# MotorConnector.net
KiCad netlist of a schematic drawn in EAGLE
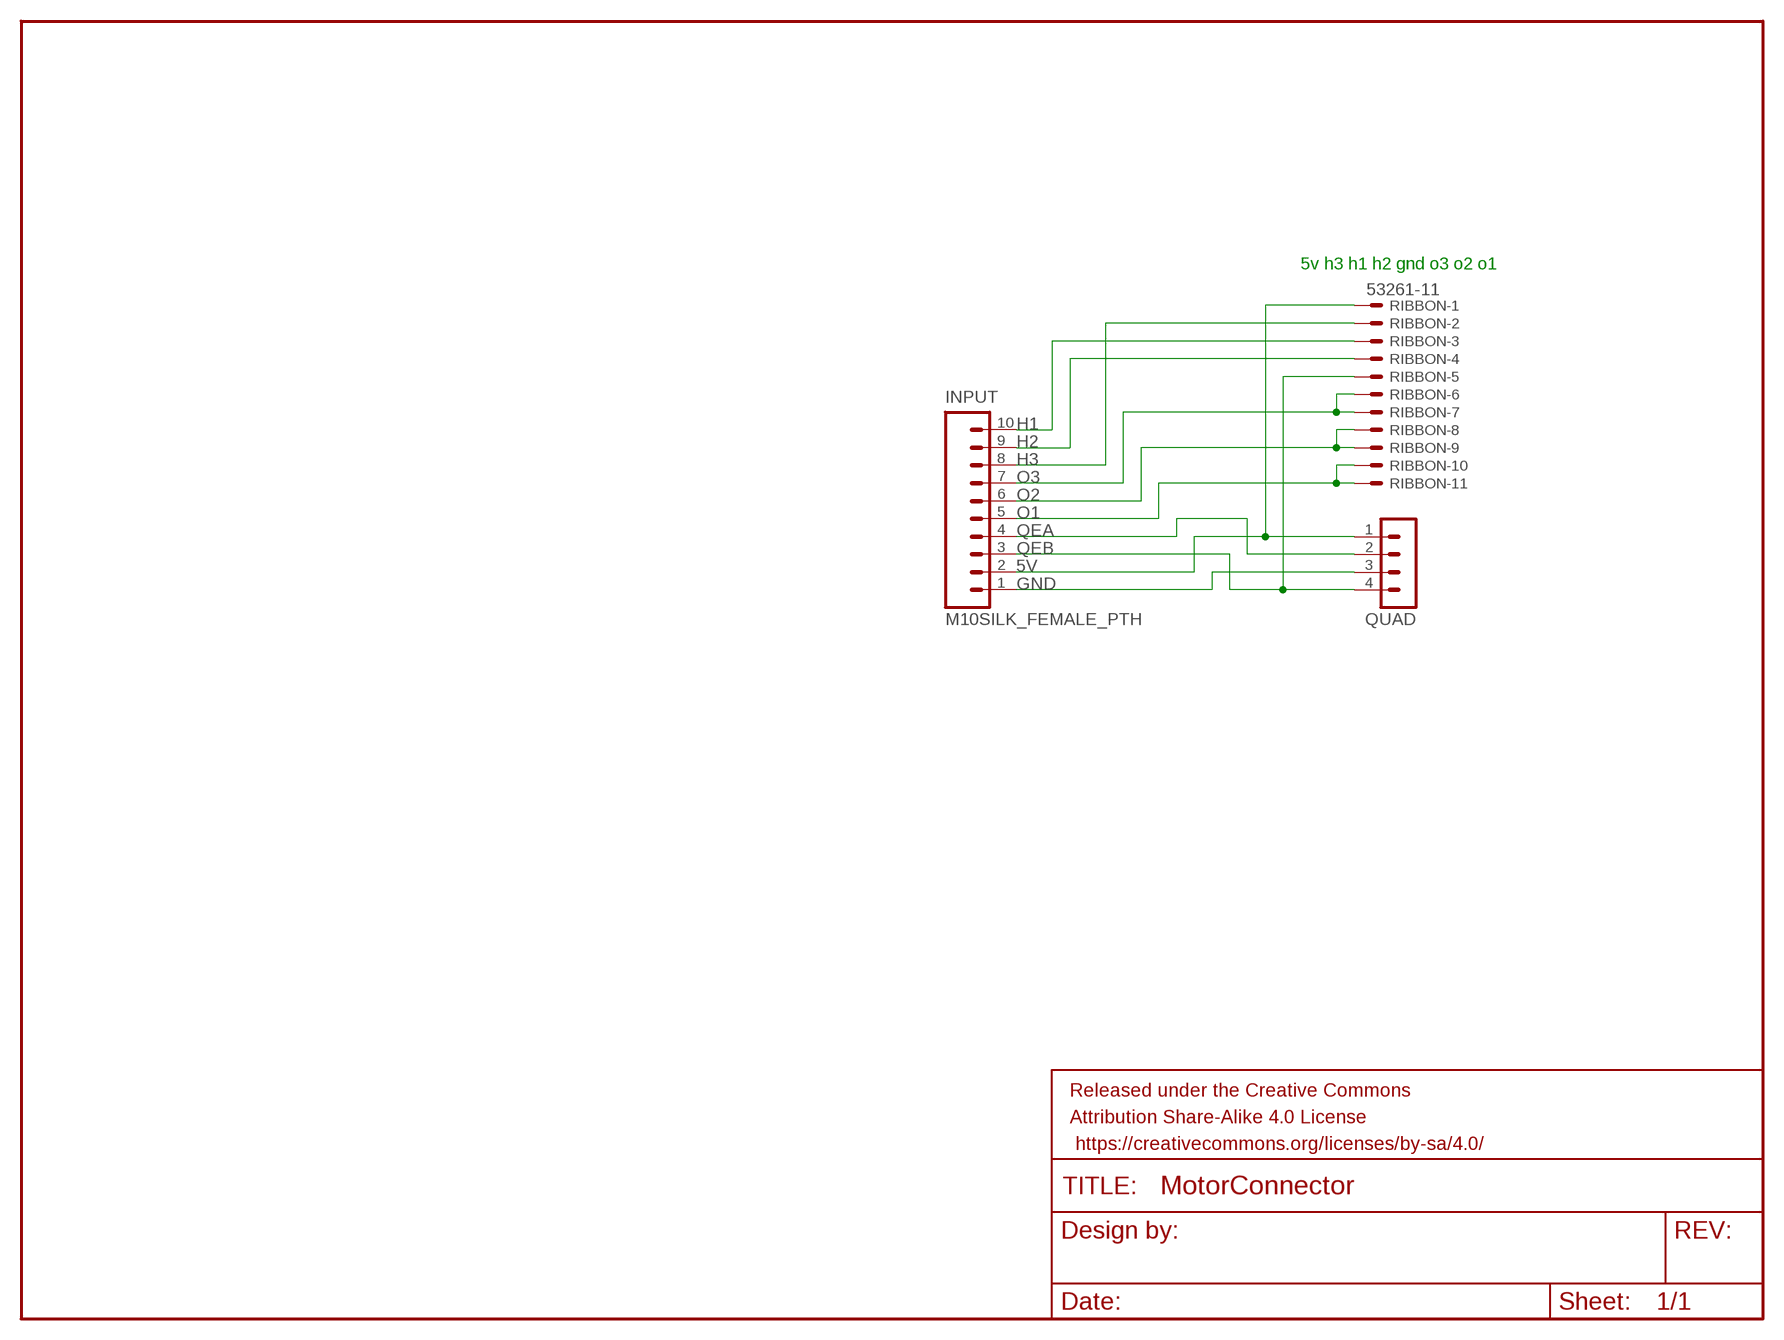
[diagram p0: schematic, sheet 1]

(export (version "E")
  (design (tool "Eeschema 10.0.6"))
  (components
    (comp (ref "FRAME1")
      (value "FRAME-LETTER")
      (footprint "eagle-import:CREATIVE_COMMONS")
      (libsource (lib "eagle-import") (part "FRAME-LETTER"))
    )
    (comp (ref "INPUT")
      (value "M10SILK_FEMALE_PTH")
      (footprint "eagle-import:1X10")
      (libsource (lib "eagle-import") (part "M10SILK_FEMALE_PTH"))
    )
    (comp (ref "QUAD")
      (value "MA04-1")
      (footprint "eagle-import:MA04-1")
      (libsource (lib "eagle-import") (part "MA04-1"))
    )
    (comp (ref "RIBBON")
      (value "53261-11")
      (footprint "eagle-import:53261-11")
      (fields (field (name "MPN") "53261-1171"))
      (libsource (lib "eagle-import") (part "53?-11261"))
    )
  )
  (nets
    (net (code "1") (name "/5V") (class "Default")
      (node (ref "INPUT") (pin "2") (pinfunction "2_2") (pintype "passive"))
      (node (ref "QUAD") (pin "1") (pinfunction "1_1") (pintype "passive"))
      (node (ref "RIBBON") (pin "1") (pinfunction "S_1") (pintype "passive"))
    )
    (net (code "2") (name "/GND") (class "Default")
      (node (ref "INPUT") (pin "1") (pinfunction "1_1") (pintype "passive"))
      (node (ref "QUAD") (pin "3") (pinfunction "3_3") (pintype "passive"))
    )
    (net (code "3") (name "/H1") (class "Default")
      (node (ref "INPUT") (pin "10") (pinfunction "10_10") (pintype "passive"))
      (node (ref "RIBBON") (pin "3") (pinfunction "S_3") (pintype "passive"))
    )
    (net (code "4") (name "/H2") (class "Default")
      (node (ref "INPUT") (pin "9") (pinfunction "9_9") (pintype "passive"))
      (node (ref "RIBBON") (pin "4") (pinfunction "S_4") (pintype "passive"))
    )
    (net (code "5") (name "/H3") (class "Default")
      (node (ref "INPUT") (pin "8") (pinfunction "8_8") (pintype "passive"))
      (node (ref "RIBBON") (pin "2") (pinfunction "S_2") (pintype "passive"))
    )
    (net (code "6") (name "/O1") (class "Default")
      (node (ref "INPUT") (pin "5") (pinfunction "5_5") (pintype "passive"))
      (node (ref "RIBBON") (pin "10") (pinfunction "S_10") (pintype "passive"))
      (node (ref "RIBBON") (pin "11") (pinfunction "S_11") (pintype "passive"))
    )
    (net (code "7") (name "/O2") (class "Default")
      (node (ref "INPUT") (pin "6") (pinfunction "6_6") (pintype "passive"))
      (node (ref "RIBBON") (pin "8") (pinfunction "S_8") (pintype "passive"))
      (node (ref "RIBBON") (pin "9") (pinfunction "S_9") (pintype "passive"))
    )
    (net (code "8") (name "/O3") (class "Default")
      (node (ref "INPUT") (pin "7") (pinfunction "7_7") (pintype "passive"))
      (node (ref "RIBBON") (pin "6") (pinfunction "S_6") (pintype "passive"))
      (node (ref "RIBBON") (pin "7") (pinfunction "S_7") (pintype "passive"))
    )
    (net (code "9") (name "/QEA") (class "Default")
      (node (ref "INPUT") (pin "4") (pinfunction "4_4") (pintype "passive"))
      (node (ref "QUAD") (pin "2") (pinfunction "2_2") (pintype "passive"))
    )
    (net (code "10") (name "/QEB") (class "Default")
      (node (ref "INPUT") (pin "3") (pinfunction "3_3") (pintype "passive"))
      (node (ref "QUAD") (pin "4") (pinfunction "4_4") (pintype "passive"))
      (node (ref "RIBBON") (pin "5") (pinfunction "S_5") (pintype "passive"))
    )
  )
)
